# RGBKeyboard.net
KiCad netlist of a schematic drawn in EAGLE
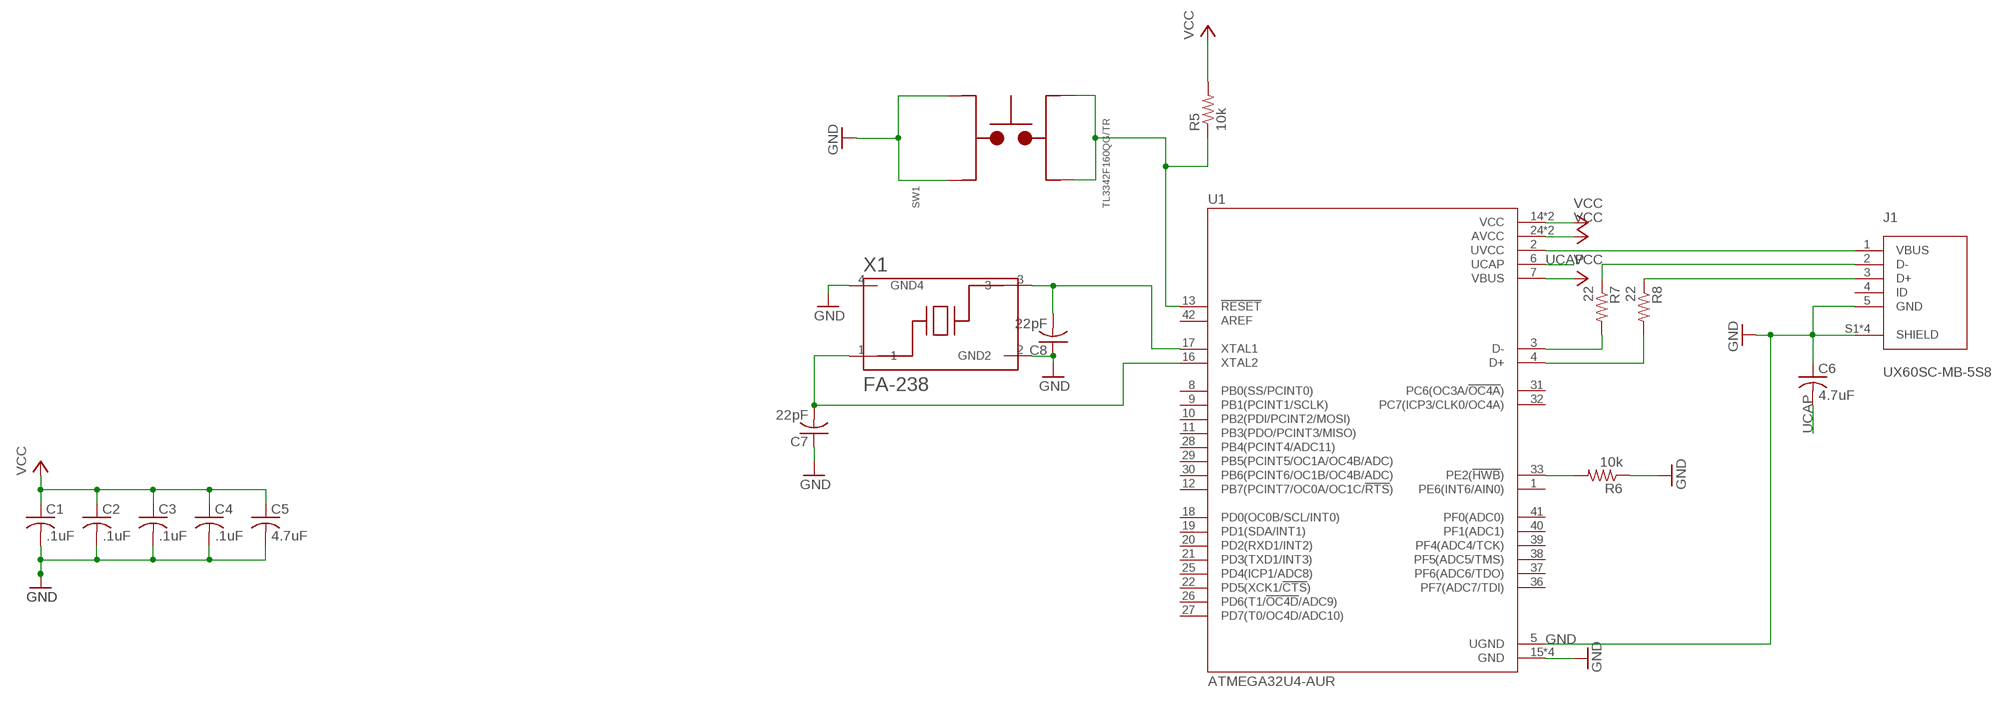
[diagram p0: schematic, sheet 1]
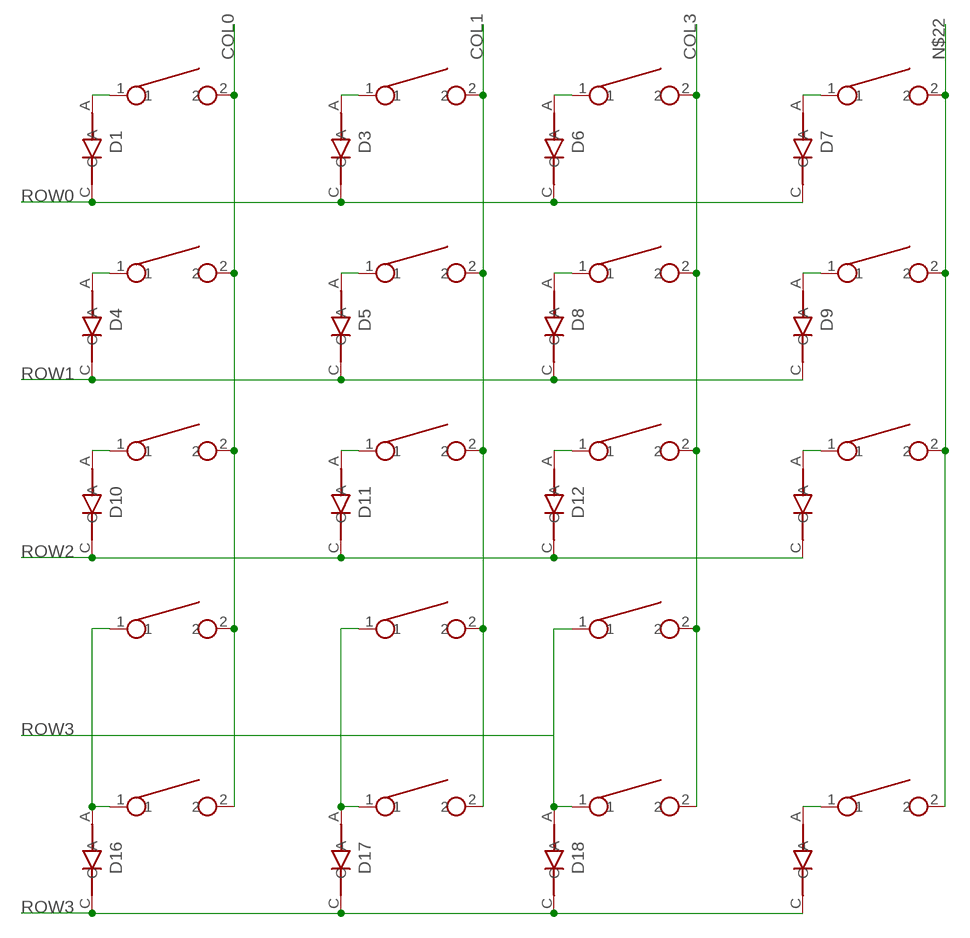
[diagram p1: schematic, sheet 2]

(export (version "E")
  (design (tool "Eeschema 10.0.6"))
  (components
    (comp (ref "D1")
      (value "BAV21W-7-F")
      (footprint "eagle-import:SOD3715X135N")
      (fields (field (name "DIGI-KEY_PART_NUMBER") "BAV21W-FDICT-ND") (field (name "MF") "Diodes Inc."))
      (libsource (lib "eagle-import") (part "BAV21W-7-F"))
    )
    (comp (ref "D3")
      (value "BAV21W-7-F")
      (footprint "eagle-import:SOD3715X135N")
      (fields (field (name "DIGI-KEY_PART_NUMBER") "BAV21W-FDICT-ND") (field (name "MF") "Diodes Inc."))
      (libsource (lib "eagle-import") (part "BAV21W-7-F"))
    )
    (comp (ref "D4")
      (value "BAV21W-7-F")
      (footprint "eagle-import:SOD3715X135N")
      (fields (field (name "DIGI-KEY_PART_NUMBER") "BAV21W-FDICT-ND") (field (name "MF") "Diodes Inc."))
      (libsource (lib "eagle-import") (part "BAV21W-7-F"))
    )
    (comp (ref "D5")
      (value "BAV21W-7-F")
      (footprint "eagle-import:SOD3715X135N")
      (fields (field (name "DIGI-KEY_PART_NUMBER") "BAV21W-FDICT-ND") (field (name "MF") "Diodes Inc."))
      (libsource (lib "eagle-import") (part "BAV21W-7-F"))
    )
    (comp (ref "D6")
      (value "BAV21W-7-F")
      (footprint "eagle-import:SOD3715X135N")
      (fields (field (name "DIGI-KEY_PART_NUMBER") "BAV21W-FDICT-ND") (field (name "MF") "Diodes Inc."))
      (libsource (lib "eagle-import") (part "BAV21W-7-F"))
    )
    (comp (ref "D7")
      (value "BAV21W-7-F")
      (footprint "eagle-import:SOD3715X135N")
      (fields (field (name "DIGI-KEY_PART_NUMBER") "BAV21W-FDICT-ND") (field (name "MF") "Diodes Inc."))
      (libsource (lib "eagle-import") (part "BAV21W-7-F"))
    )
    (comp (ref "D8")
      (value "BAV21W-7-F")
      (footprint "eagle-import:SOD3715X135N")
      (fields (field (name "DIGI-KEY_PART_NUMBER") "BAV21W-FDICT-ND") (field (name "MF") "Diodes Inc."))
      (libsource (lib "eagle-import") (part "BAV21W-7-F"))
    )
    (comp (ref "D9")
      (value "BAV21W-7-F")
      (footprint "eagle-import:SOD3715X135N")
      (fields (field (name "DIGI-KEY_PART_NUMBER") "BAV21W-FDICT-ND") (field (name "MF") "Diodes Inc."))
      (libsource (lib "eagle-import") (part "BAV21W-7-F"))
    )
    (comp (ref "D10")
      (value "BAV21W-7-F")
      (footprint "eagle-import:SOD3715X135N")
      (fields (field (name "DIGI-KEY_PART_NUMBER") "BAV21W-FDICT-ND") (field (name "MF") "Diodes Inc."))
      (libsource (lib "eagle-import") (part "BAV21W-7-F"))
    )
    (comp (ref "D11")
      (value "BAV21W-7-F")
      (footprint "eagle-import:SOD3715X135N")
      (fields (field (name "DIGI-KEY_PART_NUMBER") "BAV21W-FDICT-ND") (field (name "MF") "Diodes Inc."))
      (libsource (lib "eagle-import") (part "BAV21W-7-F"))
    )
    (comp (ref "D12")
      (value "BAV21W-7-F")
      (footprint "eagle-import:SOD3715X135N")
      (fields (field (name "DIGI-KEY_PART_NUMBER") "BAV21W-FDICT-ND") (field (name "MF") "Diodes Inc."))
      (libsource (lib "eagle-import") (part "BAV21W-7-F"))
    )
    (comp (ref "D13")
      (value "BAV21W-7-F")
      (footprint "eagle-import:SOD3715X135N")
      (fields (field (name "DIGI-KEY_PART_NUMBER") "BAV21W-FDICT-ND") (field (name "MF") "Diodes Inc."))
      (libsource (lib "eagle-import") (part "BAV21W-7-F"))
    )
    (comp (ref "D16")
      (value "BAV21W-7-F")
      (footprint "eagle-import:SOD3715X135N")
      (fields (field (name "DIGI-KEY_PART_NUMBER") "BAV21W-FDICT-ND") (field (name "MF") "Diodes Inc."))
      (libsource (lib "eagle-import") (part "BAV21W-7-F"))
    )
    (comp (ref "D17")
      (value "BAV21W-7-F")
      (footprint "eagle-import:SOD3715X135N")
      (fields (field (name "DIGI-KEY_PART_NUMBER") "BAV21W-FDICT-ND") (field (name "MF") "Diodes Inc."))
      (libsource (lib "eagle-import") (part "BAV21W-7-F"))
    )
    (comp (ref "D18")
      (value "BAV21W-7-F")
      (footprint "eagle-import:SOD3715X135N")
      (fields (field (name "DIGI-KEY_PART_NUMBER") "BAV21W-FDICT-ND") (field (name "MF") "Diodes Inc."))
      (libsource (lib "eagle-import") (part "BAV21W-7-F"))
    )
    (comp (ref "D19")
      (value "BAV21W-7-F")
      (footprint "eagle-import:SOD3715X135N")
      (fields (field (name "DIGI-KEY_PART_NUMBER") "BAV21W-FDICT-ND") (field (name "MF") "Diodes Inc."))
      (libsource (lib "eagle-import") (part "BAV21W-7-F"))
    )
    (comp (ref "U$1")
      (value "CHERRY_MX")
      (footprint "eagle-import:CHERRY_MX")
      (libsource (lib "eagle-import") (part "CHERRY_MX"))
    )
    (comp (ref "U$2")
      (value "CHERRY_MX")
      (footprint "eagle-import:CHERRY_MX")
      (libsource (lib "eagle-import") (part "CHERRY_MX"))
    )
    (comp (ref "U$3")
      (value "CHERRY_MX")
      (footprint "eagle-import:CHERRY_MX")
      (libsource (lib "eagle-import") (part "CHERRY_MX"))
    )
    (comp (ref "U$4")
      (value "CHERRY_MX")
      (footprint "eagle-import:CHERRY_MX")
      (libsource (lib "eagle-import") (part "CHERRY_MX"))
    )
    (comp (ref "U$5")
      (value "CHERRY_MX")
      (footprint "eagle-import:CHERRY_MX")
      (libsource (lib "eagle-import") (part "CHERRY_MX"))
    )
    (comp (ref "U$6")
      (value "CHERRY_MX")
      (footprint "eagle-import:CHERRY_MX")
      (libsource (lib "eagle-import") (part "CHERRY_MX"))
    )
    (comp (ref "U$7")
      (value "CHERRY_MX")
      (footprint "eagle-import:CHERRY_MX")
      (libsource (lib "eagle-import") (part "CHERRY_MX"))
    )
    (comp (ref "U$8")
      (value "CHERRY_MX")
      (footprint "eagle-import:CHERRY_MX")
      (libsource (lib "eagle-import") (part "CHERRY_MX"))
    )
    (comp (ref "U$9")
      (value "CHERRY_MX")
      (footprint "eagle-import:CHERRY_MX")
      (libsource (lib "eagle-import") (part "CHERRY_MX"))
    )
    (comp (ref "U$10")
      (value "CHERRY_MX")
      (footprint "eagle-import:CHERRY_MX")
      (libsource (lib "eagle-import") (part "CHERRY_MX"))
    )
    (comp (ref "U$11")
      (value "CHERRY_MX")
      (footprint "eagle-import:CHERRY_MX")
      (libsource (lib "eagle-import") (part "CHERRY_MX"))
    )
    (comp (ref "U$12")
      (value "CHERRY_MX")
      (footprint "eagle-import:CHERRY_MX")
      (libsource (lib "eagle-import") (part "CHERRY_MX"))
    )
    (comp (ref "U$13")
      (value "CHERRY_MXCHERRY_MX_1_2")
      (footprint "eagle-import:CHERRY_MX_1_2")
      (libsource (lib "eagle-import") (part "CHERRY_MXCHERRY_MX_1_2"))
    )
    (comp (ref "U$14")
      (value "CHERRY_MXCHERRY_MX_1_2")
      (footprint "eagle-import:CHERRY_MX_1_2")
      (libsource (lib "eagle-import") (part "CHERRY_MXCHERRY_MX_1_2"))
    )
    (comp (ref "U$15")
      (value "CHERRY_MXCHERRY_MX_1_2")
      (footprint "eagle-import:CHERRY_MX_1_2")
      (libsource (lib "eagle-import") (part "CHERRY_MXCHERRY_MX_1_2"))
    )
    (comp (ref "U$16")
      (value "CHERRY_MX")
      (footprint "eagle-import:CHERRY_MX")
      (libsource (lib "eagle-import") (part "CHERRY_MX"))
    )
    (comp (ref "U$17")
      (value "CHERRY_MX")
      (footprint "eagle-import:CHERRY_MX")
      (libsource (lib "eagle-import") (part "CHERRY_MX"))
    )
    (comp (ref "U$18")
      (value "CHERRY_MX")
      (footprint "eagle-import:CHERRY_MX")
      (libsource (lib "eagle-import") (part "CHERRY_MX"))
    )
    (comp (ref "U$19")
      (value "CHERRY_MX")
      (footprint "eagle-import:CHERRY_MX")
      (libsource (lib "eagle-import") (part "CHERRY_MX"))
    )
    (comp (ref "C1")
      (value ".1uF")
      (footprint "eagle-import:C0805")
      (libsource (lib "eagle-import") (part "C-USC0805"))
    )
    (comp (ref "C2")
      (value ".1uF")
      (footprint "eagle-import:C0805")
      (libsource (lib "eagle-import") (part "C-USC0805"))
    )
    (comp (ref "C3")
      (value ".1uF")
      (footprint "eagle-import:C0805")
      (libsource (lib "eagle-import") (part "C-USC0805"))
    )
    (comp (ref "C4")
      (value ".1uF")
      (footprint "eagle-import:C0805")
      (libsource (lib "eagle-import") (part "C-USC0805"))
    )
    (comp (ref "C5")
      (value "4.7uF")
      (footprint "eagle-import:C0805")
      (libsource (lib "eagle-import") (part "C-USC0805"))
    )
    (comp (ref "C6")
      (value "4.7uF")
      (footprint "eagle-import:C0805")
      (libsource (lib "eagle-import") (part "C-USC0805"))
    )
    (comp (ref "C7")
      (value "22pF")
      (footprint "eagle-import:C0805")
      (libsource (lib "eagle-import") (part "C-USC0805"))
    )
    (comp (ref "C8")
      (value "22pF")
      (footprint "eagle-import:C0805")
      (libsource (lib "eagle-import") (part "C-USC0805"))
    )
    (comp (ref "J1")
      (value "UX60SC-MB-5S8")
      (footprint "eagle-import:HIROSE_UX60SC-MB-5S8")
      (fields (field (name "MF") "Hirose"))
      (libsource (lib "eagle-import") (part "UX60SC-MB-5S8"))
    )
    (comp (ref "R5")
      (value "10k")
      (footprint "eagle-import:R0805")
      (libsource (lib "eagle-import") (part "R-US_R0805"))
    )
    (comp (ref "R6")
      (value "10k")
      (footprint "eagle-import:R0805")
      (libsource (lib "eagle-import") (part "R-US_R0805"))
    )
    (comp (ref "R7")
      (value "22")
      (footprint "eagle-import:R0805")
      (libsource (lib "eagle-import") (part "R-US_R0805"))
    )
    (comp (ref "R8")
      (value "22")
      (footprint "eagle-import:R0805")
      (libsource (lib "eagle-import") (part "R-US_R0805"))
    )
    (comp (ref "SW1")
      (value "TL3342F160QG/TR")
      (footprint "eagle-import:SW_TL3342F160QG_TR")
      (fields (field (name "MF") "E-Switch"))
      (libsource (lib "eagle-import") (part "TL3342F160QG/TR"))
    )
    (comp (ref "U1")
      (value "ATMEGA32U4-AUR")
      (footprint "eagle-import:QFP80P1200X1200X120-44N")
      (fields (field (name "MF") "Microchip"))
      (libsource (lib "eagle-import") (part "ATMEGA32U4-AUR"))
    )
    (comp (ref "X1")
      (value "FA-238")
      (footprint "eagle-import:OSCCC320X250X70-4N")
      (fields (field (name "MF") "EPSON"))
      (libsource (lib "eagle-import") (part "FA-238"))
    )
  )
  (nets
    (net (code "1") (name "COL0") (class "Default")
      (node (ref "U$1") (pin "2") (pinfunction "2_2") (pintype "bidirectional"))
      (node (ref "U$13") (pin "2") (pinfunction "2_2") (pintype "bidirectional"))
      (node (ref "U$17") (pin "2") (pinfunction "2_2") (pintype "bidirectional"))
      (node (ref "U$2") (pin "2") (pinfunction "2_2") (pintype "bidirectional"))
      (node (ref "U$3") (pin "2") (pinfunction "2_2") (pintype "bidirectional"))
    )
    (net (code "2") (name "COL1") (class "Default")
      (node (ref "U$14") (pin "2") (pinfunction "2_2") (pintype "bidirectional"))
      (node (ref "U$18") (pin "2") (pinfunction "2_2") (pintype "bidirectional"))
      (node (ref "U$4") (pin "2") (pinfunction "2_2") (pintype "bidirectional"))
      (node (ref "U$5") (pin "2") (pinfunction "2_2") (pintype "bidirectional"))
      (node (ref "U$6") (pin "2") (pinfunction "2_2") (pintype "bidirectional"))
    )
    (net (code "3") (name "COL3") (class "Default")
      (node (ref "U$15") (pin "2") (pinfunction "2_2") (pintype "bidirectional"))
      (node (ref "U$19") (pin "2") (pinfunction "2_2") (pintype "bidirectional"))
      (node (ref "U$7") (pin "2") (pinfunction "2_2") (pintype "bidirectional"))
      (node (ref "U$8") (pin "2") (pinfunction "2_2") (pintype "bidirectional"))
      (node (ref "U$9") (pin "2") (pinfunction "2_2") (pintype "bidirectional"))
    )
    (net (code "4") (name "GND") (class "Default")
      (node (ref "C1") (pin "2") (pinfunction "2_2") (pintype "passive"))
      (node (ref "C2") (pin "2") (pinfunction "2_2") (pintype "passive"))
      (node (ref "C3") (pin "2") (pinfunction "2_2") (pintype "passive"))
      (node (ref "C4") (pin "2") (pinfunction "2_2") (pintype "passive"))
      (node (ref "C5") (pin "2") (pinfunction "2_2") (pintype "passive"))
      (node (ref "C6") (pin "1") (pinfunction "1_1") (pintype "passive"))
      (node (ref "C7") (pin "1") (pinfunction "1_1") (pintype "passive"))
      (node (ref "C8") (pin "1") (pinfunction "1_1") (pintype "passive"))
      (node (ref "J1") (pin "5") (pinfunction "GND_5") (pintype "power_in"))
      (node (ref "J1") (pin "S1") (pinfunction "SHIELD_S1") (pintype "power_in"))
      (node (ref "J1") (pin "S2") (pinfunction "SHIELD_S2") (pintype "power_in"))
      (node (ref "J1") (pin "S3") (pinfunction "SHIELD_S3") (pintype "power_in"))
      (node (ref "J1") (pin "S4") (pinfunction "SHIELD_S4") (pintype "power_in"))
      (node (ref "R6") (pin "1") (pinfunction "1_1") (pintype "passive"))
      (node (ref "SW1") (pin "3") (pinfunction "3_3") (pintype "passive"))
      (node (ref "SW1") (pin "4") (pinfunction "4_4") (pintype "passive"))
      (node (ref "U1") (pin "15") (pinfunction "GND_15") (pintype "power_in"))
      (node (ref "U1") (pin "23") (pinfunction "GND_23") (pintype "power_in"))
      (node (ref "U1") (pin "35") (pinfunction "GND_35") (pintype "power_in"))
      (node (ref "U1") (pin "43") (pinfunction "GND_43") (pintype "power_in"))
      (node (ref "U1") (pin "5") (pinfunction "UGND_5") (pintype "power_in"))
      (node (ref "X1") (pin "2") (pinfunction "GND2_2") (pintype "passive"))
      (node (ref "X1") (pin "4") (pinfunction "GND4_4") (pintype "passive"))
    )
    (net (code "5") (name "N$22") (class "Default")
      (node (ref "U$10") (pin "2") (pinfunction "2_2") (pintype "bidirectional"))
      (node (ref "U$11") (pin "2") (pinfunction "2_2") (pintype "bidirectional"))
      (node (ref "U$12") (pin "2") (pinfunction "2_2") (pintype "bidirectional"))
      (node (ref "U$16") (pin "2") (pinfunction "2_2") (pintype "bidirectional"))
    )
    (net (code "6") (name "Net-(D1-PadA)") (class "Default")
      (node (ref "D1") (pin "A") (pinfunction "A_A") (pintype "passive"))
      (node (ref "U$1") (pin "1") (pinfunction "1_1") (pintype "bidirectional"))
    )
    (net (code "7") (name "Net-(D3-PadA)") (class "Default")
      (node (ref "D3") (pin "A") (pinfunction "A_A") (pintype "passive"))
      (node (ref "U$4") (pin "1") (pinfunction "1_1") (pintype "bidirectional"))
    )
    (net (code "8") (name "Net-(D4-PadA)") (class "Default")
      (node (ref "D4") (pin "A") (pinfunction "A_A") (pintype "passive"))
      (node (ref "U$2") (pin "1") (pinfunction "1_1") (pintype "bidirectional"))
    )
    (net (code "9") (name "Net-(D5-PadA)") (class "Default")
      (node (ref "D5") (pin "A") (pinfunction "A_A") (pintype "passive"))
      (node (ref "U$5") (pin "1") (pinfunction "1_1") (pintype "bidirectional"))
    )
    (net (code "10") (name "Net-(D6-PadA)") (class "Default")
      (node (ref "D6") (pin "A") (pinfunction "A_A") (pintype "passive"))
      (node (ref "U$7") (pin "1") (pinfunction "1_1") (pintype "bidirectional"))
    )
    (net (code "11") (name "Net-(D7-PadA)") (class "Default")
      (node (ref "D7") (pin "A") (pinfunction "A_A") (pintype "passive"))
      (node (ref "U$12") (pin "1") (pinfunction "1_1") (pintype "bidirectional"))
    )
    (net (code "12") (name "Net-(D8-PadA)") (class "Default")
      (node (ref "D8") (pin "A") (pinfunction "A_A") (pintype "passive"))
      (node (ref "U$8") (pin "1") (pinfunction "1_1") (pintype "bidirectional"))
    )
    (net (code "13") (name "Net-(D9-PadA)") (class "Default")
      (node (ref "D9") (pin "A") (pinfunction "A_A") (pintype "passive"))
      (node (ref "U$10") (pin "1") (pinfunction "1_1") (pintype "bidirectional"))
    )
    (net (code "14") (name "Net-(D10-PadA)") (class "Default")
      (node (ref "D10") (pin "A") (pinfunction "A_A") (pintype "passive"))
      (node (ref "U$3") (pin "1") (pinfunction "1_1") (pintype "bidirectional"))
    )
    (net (code "15") (name "Net-(D11-PadA)") (class "Default")
      (node (ref "D11") (pin "A") (pinfunction "A_A") (pintype "passive"))
      (node (ref "U$6") (pin "1") (pinfunction "1_1") (pintype "bidirectional"))
    )
    (net (code "16") (name "Net-(D12-PadA)") (class "Default")
      (node (ref "D12") (pin "A") (pinfunction "A_A") (pintype "passive"))
      (node (ref "U$9") (pin "1") (pinfunction "1_1") (pintype "bidirectional"))
    )
    (net (code "17") (name "Net-(D13-PadA)") (class "Default")
      (node (ref "D13") (pin "A") (pinfunction "A_A") (pintype "passive"))
      (node (ref "U$11") (pin "1") (pinfunction "1_1") (pintype "bidirectional"))
    )
    (net (code "18") (name "Net-(D16-PadA)") (class "Default")
      (node (ref "D16") (pin "A") (pinfunction "A_A") (pintype "passive"))
      (node (ref "U$13") (pin "1") (pinfunction "1_1") (pintype "bidirectional"))
      (node (ref "U$17") (pin "1") (pinfunction "1_1") (pintype "bidirectional"))
    )
    (net (code "19") (name "Net-(D17-PadA)") (class "Default")
      (node (ref "D17") (pin "A") (pinfunction "A_A") (pintype "passive"))
      (node (ref "U$14") (pin "1") (pinfunction "1_1") (pintype "bidirectional"))
      (node (ref "U$18") (pin "1") (pinfunction "1_1") (pintype "bidirectional"))
    )
    (net (code "20") (name "Net-(D18-PadA)") (class "Default")
      (node (ref "D18") (pin "A") (pinfunction "A_A") (pintype "passive"))
      (node (ref "U$15") (pin "1") (pinfunction "1_1") (pintype "bidirectional"))
      (node (ref "U$19") (pin "1") (pinfunction "1_1") (pintype "bidirectional"))
    )
    (net (code "21") (name "Net-(D19-PadA)") (class "Default")
      (node (ref "D19") (pin "A") (pinfunction "A_A") (pintype "passive"))
      (node (ref "U$16") (pin "1") (pinfunction "1_1") (pintype "bidirectional"))
    )
    (net (code "22") (name "Net-(J1-D+)") (class "Default")
      (node (ref "J1") (pin "3") (pinfunction "D+_3") (pintype "bidirectional"))
      (node (ref "R8") (pin "1") (pinfunction "1_1") (pintype "passive"))
    )
    (net (code "23") (name "Net-(J1-D-)") (class "Default")
      (node (ref "J1") (pin "2") (pinfunction "D-_2") (pintype "bidirectional"))
      (node (ref "R7") (pin "1") (pinfunction "1_1") (pintype "passive"))
    )
    (net (code "24") (name "Net-(J1-VBUS)") (class "Default")
      (node (ref "J1") (pin "1") (pinfunction "VBUS_1") (pintype "power_in"))
      (node (ref "U1") (pin "2") (pinfunction "UVCC_2") (pintype "power_in"))
    )
    (net (code "25") (name "Net-(U1-D+)") (class "Default")
      (node (ref "R8") (pin "2") (pinfunction "2_2") (pintype "passive"))
      (node (ref "U1") (pin "4") (pinfunction "D+_4") (pintype "bidirectional"))
    )
    (net (code "26") (name "Net-(U1-D-)") (class "Default")
      (node (ref "R7") (pin "2") (pinfunction "2_2") (pintype "passive"))
      (node (ref "U1") (pin "3") (pinfunction "D-_3") (pintype "bidirectional"))
    )
    (net (code "27") (name "Net-(U1-PE2(~{HWB}))") (class "Default")
      (node (ref "R6") (pin "2") (pinfunction "2_2") (pintype "passive"))
      (node (ref "U1") (pin "33") (pinfunction "PE2(~{HWB})_33") (pintype "bidirectional"))
    )
    (net (code "28") (name "Net-(U1-XTAL1)") (class "Default")
      (node (ref "C8") (pin "2") (pinfunction "2_2") (pintype "passive"))
      (node (ref "U1") (pin "17") (pinfunction "XTAL1_17") (pintype "input"))
      (node (ref "X1") (pin "3") (pinfunction "3_3") (pintype "passive"))
    )
    (net (code "29") (name "Net-(U1-XTAL2)") (class "Default")
      (node (ref "C7") (pin "2") (pinfunction "2_2") (pintype "passive"))
      (node (ref "U1") (pin "16") (pinfunction "XTAL2_16") (pintype "output"))
      (node (ref "X1") (pin "1") (pinfunction "1_1") (pintype "passive"))
    )
    (net (code "30") (name "Net-(U1-~{RESET})") (class "Default")
      (node (ref "R5") (pin "1") (pinfunction "1_1") (pintype "passive"))
      (node (ref "SW1") (pin "1") (pinfunction "1_1") (pintype "passive"))
      (node (ref "SW1") (pin "2") (pinfunction "2_2") (pintype "passive"))
      (node (ref "U1") (pin "13") (pinfunction "~{RESET}_13") (pintype "input"))
    )
    (net (code "31") (name "ROW0") (class "Default")
      (node (ref "D1") (pin "C") (pinfunction "C_C") (pintype "passive"))
      (node (ref "D3") (pin "C") (pinfunction "C_C") (pintype "passive"))
      (node (ref "D6") (pin "C") (pinfunction "C_C") (pintype "passive"))
      (node (ref "D7") (pin "C") (pinfunction "C_C") (pintype "passive"))
    )
    (net (code "32") (name "ROW1") (class "Default")
      (node (ref "D4") (pin "C") (pinfunction "C_C") (pintype "passive"))
      (node (ref "D5") (pin "C") (pinfunction "C_C") (pintype "passive"))
      (node (ref "D8") (pin "C") (pinfunction "C_C") (pintype "passive"))
      (node (ref "D9") (pin "C") (pinfunction "C_C") (pintype "passive"))
    )
    (net (code "33") (name "ROW2") (class "Default")
      (node (ref "D10") (pin "C") (pinfunction "C_C") (pintype "passive"))
      (node (ref "D11") (pin "C") (pinfunction "C_C") (pintype "passive"))
      (node (ref "D12") (pin "C") (pinfunction "C_C") (pintype "passive"))
      (node (ref "D13") (pin "C") (pinfunction "C_C") (pintype "passive"))
    )
    (net (code "34") (name "ROW3") (class "Default")
      (node (ref "D16") (pin "C") (pinfunction "C_C") (pintype "passive"))
      (node (ref "D17") (pin "C") (pinfunction "C_C") (pintype "passive"))
      (node (ref "D18") (pin "C") (pinfunction "C_C") (pintype "passive"))
      (node (ref "D19") (pin "C") (pinfunction "C_C") (pintype "passive"))
    )
    (net (code "35") (name "UCAP") (class "Default")
      (node (ref "C6") (pin "2") (pinfunction "2_2") (pintype "passive"))
      (node (ref "U1") (pin "6") (pinfunction "UCAP_6") (pintype "power_in"))
    )
    (net (code "36") (name "VCC") (class "Default")
      (node (ref "C1") (pin "1") (pinfunction "1_1") (pintype "passive"))
      (node (ref "C2") (pin "1") (pinfunction "1_1") (pintype "passive"))
      (node (ref "C3") (pin "1") (pinfunction "1_1") (pintype "passive"))
      (node (ref "C4") (pin "1") (pinfunction "1_1") (pintype "passive"))
      (node (ref "C5") (pin "1") (pinfunction "1_1") (pintype "passive"))
      (node (ref "R5") (pin "2") (pinfunction "2_2") (pintype "passive"))
      (node (ref "U1") (pin "14") (pinfunction "VCC_14") (pintype "power_in"))
      (node (ref "U1") (pin "24") (pinfunction "AVCC_24") (pintype "power_in"))
      (node (ref "U1") (pin "34") (pinfunction "VCC_34") (pintype "power_in"))
      (node (ref "U1") (pin "44") (pinfunction "AVCC_44") (pintype "power_in"))
      (node (ref "U1") (pin "7") (pinfunction "VBUS_7") (pintype "power_in"))
    )
    (net (code "37") (name "unconnected-(J1-ID-Pad4)") (class "Default")
      (node (ref "J1") (pin "4") (pinfunction "ID_4") (pintype "bidirectional"))
    )
    (net (code "38") (name "unconnected-(U1-AREF-Pad42)") (class "Default")
      (node (ref "U1") (pin "42") (pinfunction "AREF_42") (pintype "input"))
    )
    (net (code "39") (name "unconnected-(U1-PB0(SS{slash}PCINT0)-Pad8)") (class "Default")
      (node (ref "U1") (pin "8") (pinfunction "PB0(SS/PCINT0)_8") (pintype "bidirectional"))
    )
    (net (code "40") (name "unconnected-(U1-PB1(PCINT1{slash}SCLK)-Pad9)") (class "Default")
      (node (ref "U1") (pin "9") (pinfunction "PB1(PCINT1/SCLK)_9") (pintype "bidirectional"))
    )
    (net (code "41") (name "unconnected-(U1-PB2(PDI{slash}PCINT2{slash}MOSI)-Pad10)") (class "Default")
      (node (ref "U1") (pin "10") (pinfunction "PB2(PDI/PCINT2/MOSI)_10") (pintype "bidirectional"))
    )
    (net (code "42") (name "unconnected-(U1-PB3(PDO{slash}PCINT3{slash}MISO)-Pad11)") (class "Default")
      (node (ref "U1") (pin "11") (pinfunction "PB3(PDO/PCINT3/MISO)_11") (pintype "bidirectional"))
    )
    (net (code "43") (name "unconnected-(U1-PB4(PCINT4{slash}ADC11)-Pad28)") (class "Default")
      (node (ref "U1") (pin "28") (pinfunction "PB4(PCINT4/ADC11)_28") (pintype "bidirectional"))
    )
    (net (code "44") (name "unconnected-(U1-PB5(PCINT5{slash}OC1A{slash}OC4B{slash}ADC)-Pad29)") (class "Default")
      (node (ref "U1") (pin "29") (pinfunction "PB5(PCINT5/OC1A/OC4B/ADC)_29") (pintype "bidirectional"))
    )
    (net (code "45") (name "unconnected-(U1-PB6(PCINT6{slash}OC1B{slash}OC4B{slash}ADC)-Pad30)") (class "Default")
      (node (ref "U1") (pin "30") (pinfunction "PB6(PCINT6/OC1B/OC4B/ADC)_30") (pintype "bidirectional"))
    )
    (net (code "46") (name "unconnected-(U1-PB7(PCINT7{slash}OC0A{slash}OC1C{slash}~{RTS})-Pad12)") (class "Default")
      (node (ref "U1") (pin "12") (pinfunction "PB7(PCINT7/OC0A/OC1C/~{RTS})_12") (pintype "bidirectional"))
    )
    (net (code "47") (name "unconnected-(U1-PC6(OC3A{slash}~{OC4A})-Pad31)") (class "Default")
      (node (ref "U1") (pin "31") (pinfunction "PC6(OC3A/~{OC4A})_31") (pintype "bidirectional"))
    )
    (net (code "48") (name "unconnected-(U1-PC7(ICP3{slash}CLK0{slash}OC4A)-Pad32)") (class "Default")
      (node (ref "U1") (pin "32") (pinfunction "PC7(ICP3/CLK0/OC4A)_32") (pintype "bidirectional"))
    )
    (net (code "49") (name "unconnected-(U1-PD0(OC0B{slash}SCL{slash}INT0)-Pad18)") (class "Default")
      (node (ref "U1") (pin "18") (pinfunction "PD0(OC0B/SCL/INT0)_18") (pintype "bidirectional"))
    )
    (net (code "50") (name "unconnected-(U1-PD1(SDA{slash}INT1)-Pad19)") (class "Default")
      (node (ref "U1") (pin "19") (pinfunction "PD1(SDA/INT1)_19") (pintype "bidirectional"))
    )
    (net (code "51") (name "unconnected-(U1-PD2(RXD1{slash}INT2)-Pad20)") (class "Default")
      (node (ref "U1") (pin "20") (pinfunction "PD2(RXD1/INT2)_20") (pintype "bidirectional"))
    )
    (net (code "52") (name "unconnected-(U1-PD3(TXD1{slash}INT3)-Pad21)") (class "Default")
      (node (ref "U1") (pin "21") (pinfunction "PD3(TXD1/INT3)_21") (pintype "bidirectional"))
    )
    (net (code "53") (name "unconnected-(U1-PD4(ICP1{slash}ADC8)-Pad25)") (class "Default")
      (node (ref "U1") (pin "25") (pinfunction "PD4(ICP1/ADC8)_25") (pintype "bidirectional"))
    )
    (net (code "54") (name "unconnected-(U1-PD5(XCK1{slash}~{CTS})-Pad22)") (class "Default")
      (node (ref "U1") (pin "22") (pinfunction "PD5(XCK1/~{CTS})_22") (pintype "bidirectional"))
    )
    (net (code "55") (name "unconnected-(U1-PD6(T1{slash}~{OC4D}{slash}ADC9)-Pad26)") (class "Default")
      (node (ref "U1") (pin "26") (pinfunction "PD6(T1/~{OC4D}/ADC9)_26") (pintype "bidirectional"))
    )
    (net (code "56") (name "unconnected-(U1-PD7(T0{slash}OC4D{slash}ADC10)-Pad27)") (class "Default")
      (node (ref "U1") (pin "27") (pinfunction "PD7(T0/OC4D/ADC10)_27") (pintype "bidirectional"))
    )
    (net (code "57") (name "unconnected-(U1-PE6(INT6{slash}AIN0)-Pad1)") (class "Default")
      (node (ref "U1") (pin "1") (pinfunction "PE6(INT6/AIN0)_1") (pintype "bidirectional"))
    )
    (net (code "58") (name "unconnected-(U1-PF0(ADC0)-Pad41)") (class "Default")
      (node (ref "U1") (pin "41") (pinfunction "PF0(ADC0)_41") (pintype "bidirectional"))
    )
    (net (code "59") (name "unconnected-(U1-PF1(ADC1)-Pad40)") (class "Default")
      (node (ref "U1") (pin "40") (pinfunction "PF1(ADC1)_40") (pintype "bidirectional"))
    )
    (net (code "60") (name "unconnected-(U1-PF4(ADC4{slash}TCK)-Pad39)") (class "Default")
      (node (ref "U1") (pin "39") (pinfunction "PF4(ADC4/TCK)_39") (pintype "bidirectional"))
    )
    (net (code "61") (name "unconnected-(U1-PF5(ADC5{slash}TMS)-Pad38)") (class "Default")
      (node (ref "U1") (pin "38") (pinfunction "PF5(ADC5/TMS)_38") (pintype "bidirectional"))
    )
    (net (code "62") (name "unconnected-(U1-PF6(ADC6{slash}TDO)-Pad37)") (class "Default")
      (node (ref "U1") (pin "37") (pinfunction "PF6(ADC6/TDO)_37") (pintype "bidirectional"))
    )
    (net (code "63") (name "unconnected-(U1-PF7(ADC7{slash}TDI)-Pad36)") (class "Default")
      (node (ref "U1") (pin "36") (pinfunction "PF7(ADC7/TDI)_36") (pintype "bidirectional"))
    )
  )
)
